# BT.net
KiCad netlist of a schematic drawn in EasyEDA
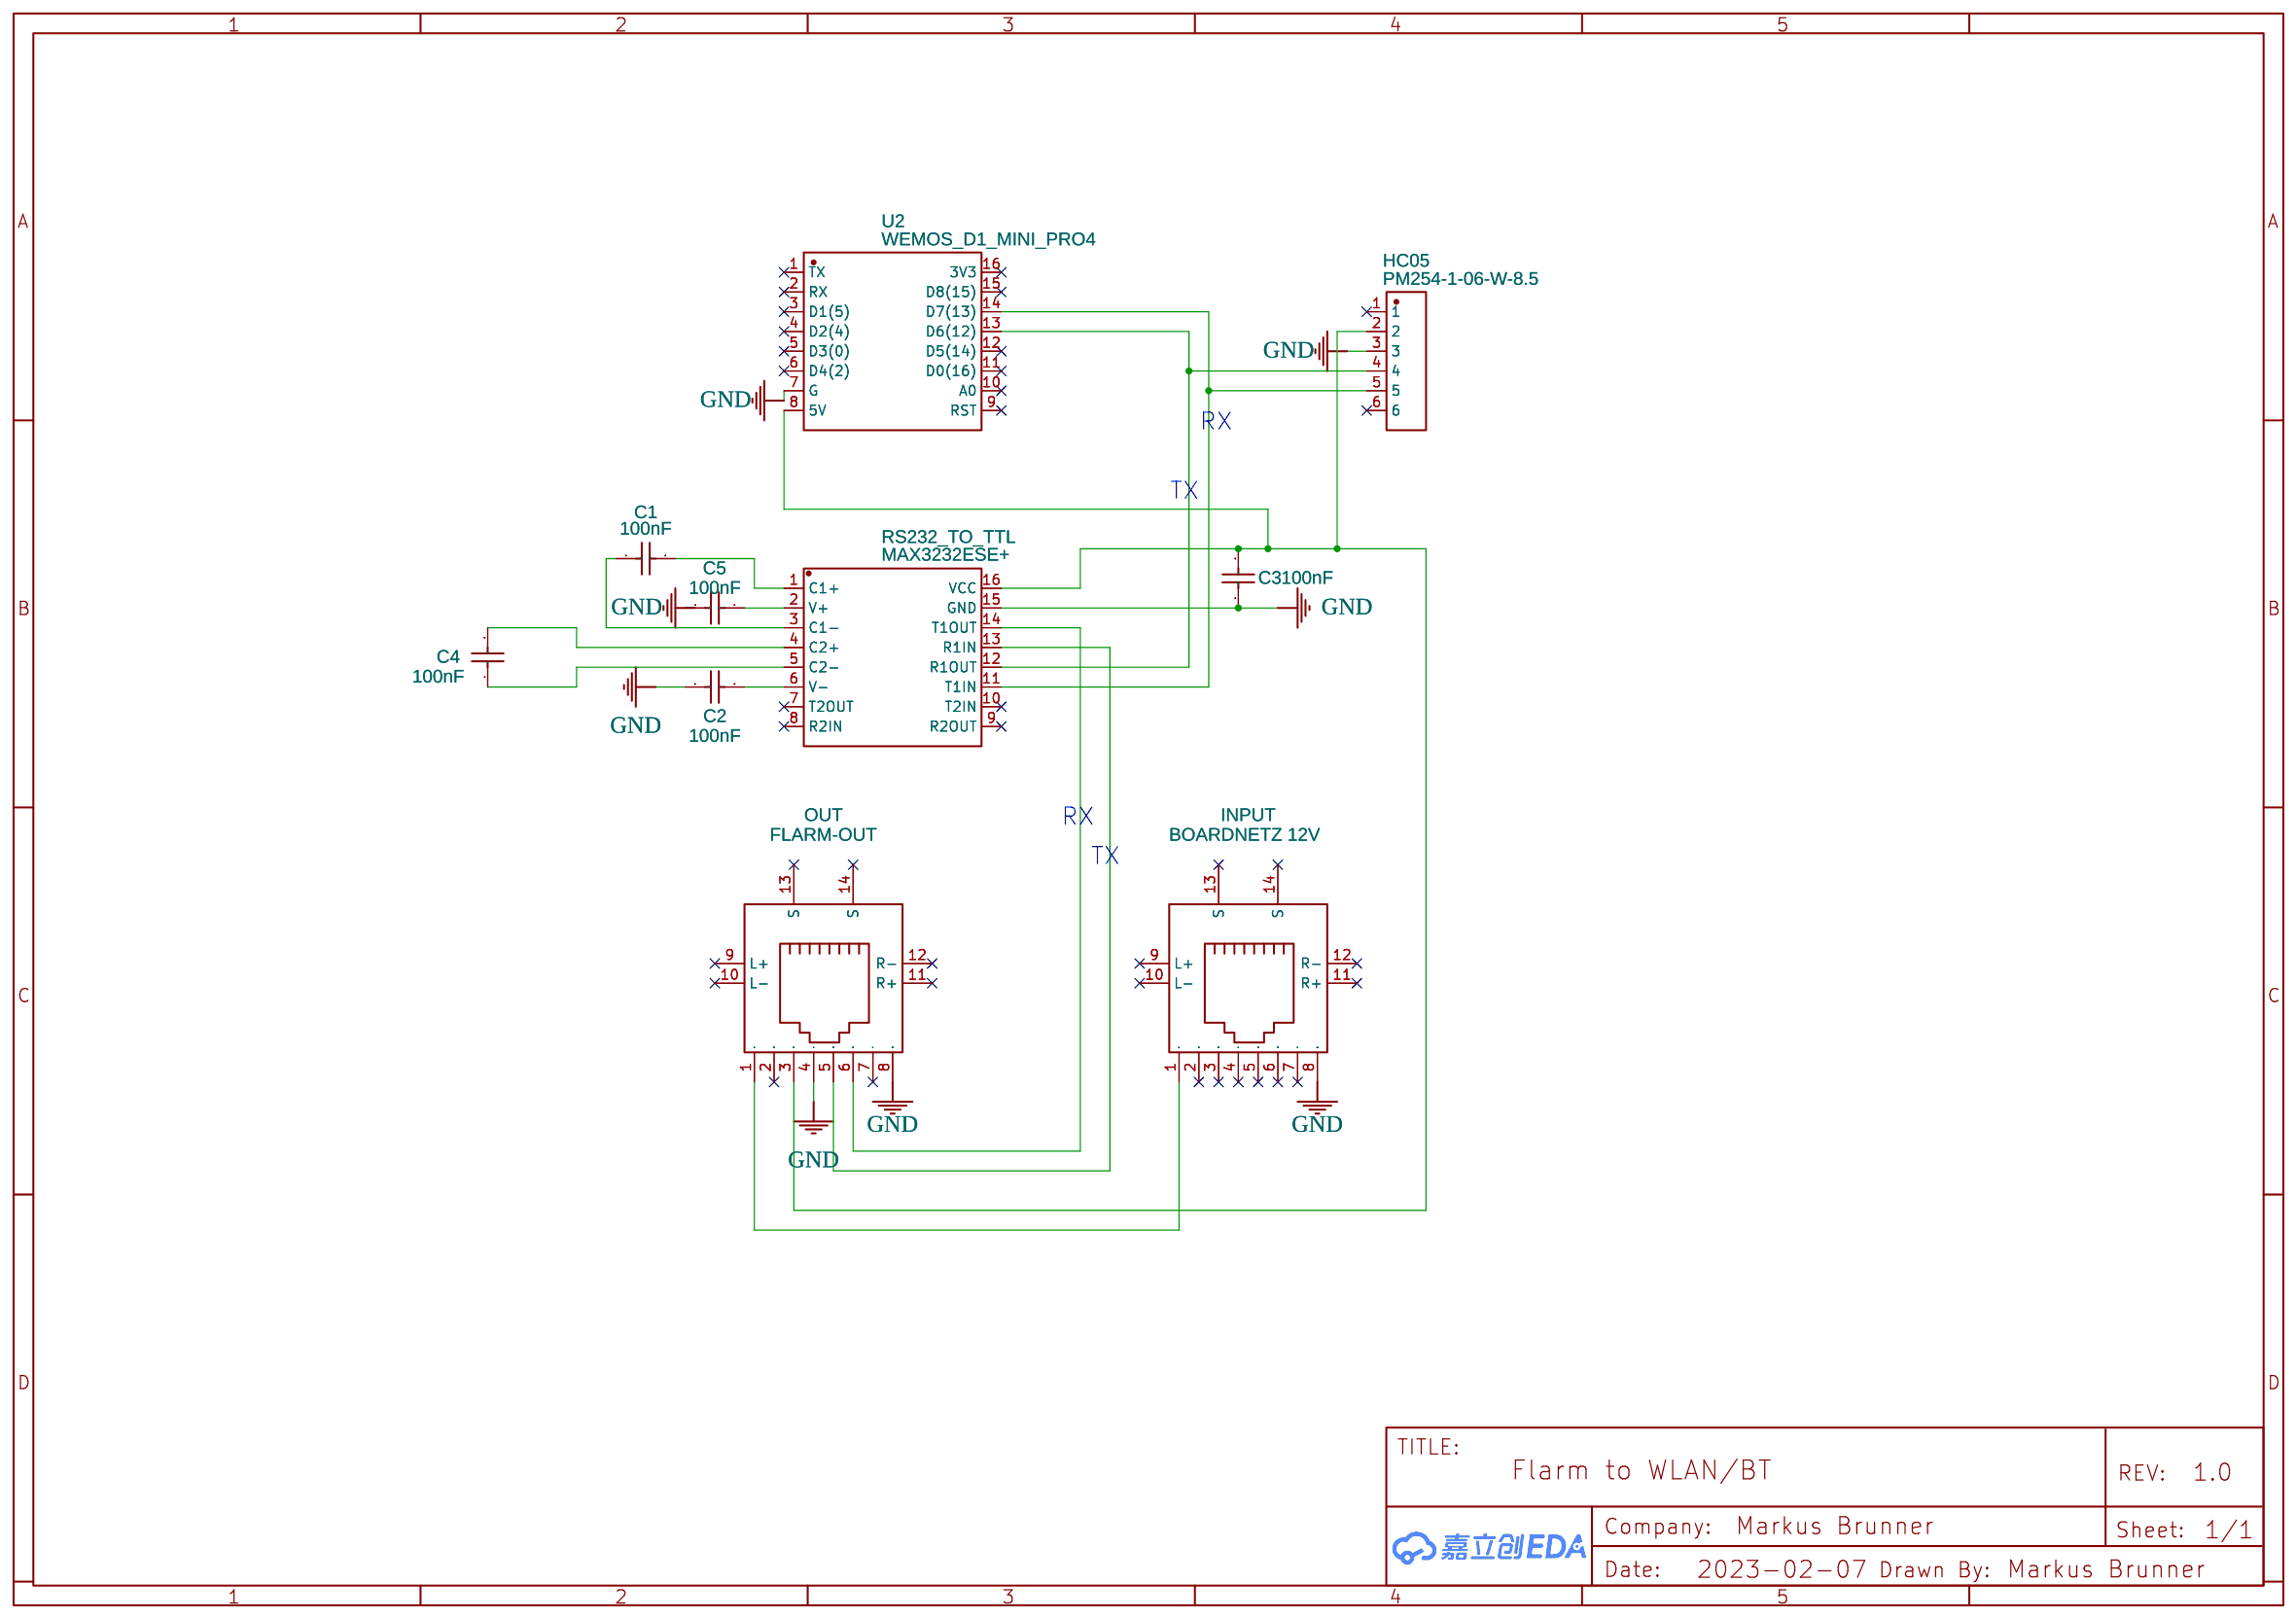
[diagram p0: schematic sheet]

(export (version "E")
  (design (tool "Eeschema 10.0.6"))
  (components
    (comp (ref "C1")
      (value "100nF")
      (fields
        (field (name "BOM_Manufacturer Part") "CL05B104KO5NNNC")
        (field (name "BOM_Supplier Part") "C1525")
      )
      (libsource (lib "") (part "CL05B104KO5NNNC"))
    )
    (comp (ref "C2")
      (value "100nF")
      (fields
        (field (name "BOM_Manufacturer Part") "CL05B104KO5NNNC")
        (field (name "BOM_Supplier Part") "C1525")
      )
      (libsource (lib "") (part "CL05B104KO5NNNC"))
    )
    (comp (ref "C3")
      (value "100nF")
      (fields
        (field (name "BOM_Manufacturer Part") "CL05B104KO5NNNC")
        (field (name "BOM_Supplier Part") "C1525")
      )
      (libsource (lib "") (part "CL05B104KO5NNNC_1"))
    )
    (comp (ref "C4")
      (value "100nF")
      (fields
        (field (name "BOM_Manufacturer Part") "CL05B104KO5NNNC")
        (field (name "BOM_Supplier Part") "C1525")
      )
      (libsource (lib "") (part "CL05B104KO5NNNC_1"))
    )
    (comp (ref "C5")
      (value "100nF")
      (fields
        (field (name "BOM_Manufacturer Part") "CL05B104KO5NNNC")
        (field (name "BOM_Supplier Part") "C1525")
      )
      (libsource (lib "") (part "CL05B104KO5NNNC"))
    )
    (comp (ref "HC05")
      (value "PM254-1-06-W-8.5")
      (fields (field (name "BOM_Supplier Part") "C2897388"))
      (libsource (lib "") (part "PM254-1-06-W-8.5"))
    )
    (comp (ref "INPUT")
      (value "BOARDNETZ 12V")
      (fields
        (field (name "BOM_Manufacturer Part") "R-RJ45R08P-C000")
        (field (name "BOM_Supplier Part") "C386757")
      )
      (libsource (lib "") (part "R-RJ45R08P-C000"))
    )
    (comp (ref "OUT")
      (value "FLARM-OUT")
      (fields
        (field (name "BOM_Manufacturer Part") "R-RJ45R08P-C000")
        (field (name "BOM_Supplier Part") "C386757")
      )
      (libsource (lib "") (part "R-RJ45R08P-C000_1"))
    )
    (comp (ref "RS232_TO_TTL")
      (value "MAX3232ESE+")
      (fields (field (name "BOM_Supplier Part") "C143435"))
      (libsource (lib "") (part "MAX3232ESE+"))
    )
    (comp (ref "U2")
      (value "WEMOS_D1_MINI_PRO4")
      (fields
        (field (name "BOM_Manufacturer Part") "Wemos_D1_mini_Pro4")
        (field (name "BOM_Supplier Part") "C2837266")
      )
      (libsource (lib "") (part "WEMOS_D1_MINI_PRO4"))
    )
  )
  (nets
    (net (code "1") (name "GND") (class "Default")
      (node (ref "C2") (pin "1") (pinfunction "1_1") (pintype "input"))
      (node (ref "C3") (pin "1") (pinfunction "1_1") (pintype "input"))
      (node (ref "C5") (pin "1") (pinfunction "1_1") (pintype "input"))
      (node (ref "HC05") (pin "3") (pinfunction "3_3") (pintype "unspecified"))
      (node (ref "INPUT") (pin "8") (pinfunction "8_8") (pintype "unspecified"))
      (node (ref "OUT") (pin "4") (pinfunction "4_4") (pintype "unspecified"))
      (node (ref "OUT") (pin "8") (pinfunction "8_8") (pintype "unspecified"))
      (node (ref "RS232_TO_TTL") (pin "15") (pinfunction "GND_15") (pintype "unspecified"))
      (node (ref "U2") (pin "7") (pinfunction "G_7") (pintype "unspecified"))
    )
    (net (code "2") (name "Net-(INPUT-Pad1)") (class "Default")
      (node (ref "INPUT") (pin "1") (pinfunction "1_1") (pintype "unspecified"))
      (node (ref "OUT") (pin "1") (pinfunction "1_1") (pintype "unspecified"))
    )
    (net (code "3") (name "Net-(RS232_TO_TTL-C1+)") (class "Default")
      (node (ref "C1") (pin "2") (pinfunction "2_2") (pintype "input"))
      (node (ref "RS232_TO_TTL") (pin "1") (pinfunction "C1+_1") (pintype "unspecified"))
    )
    (net (code "4") (name "Net-(RS232_TO_TTL-C1-)") (class "Default")
      (node (ref "C1") (pin "1") (pinfunction "1_1") (pintype "input"))
      (node (ref "RS232_TO_TTL") (pin "3") (pinfunction "C1-_3") (pintype "unspecified"))
    )
    (net (code "5") (name "Net-(RS232_TO_TTL-C2+)") (class "Default")
      (node (ref "C4") (pin "2") (pinfunction "2_2") (pintype "input"))
      (node (ref "RS232_TO_TTL") (pin "4") (pinfunction "C2+_4") (pintype "unspecified"))
    )
    (net (code "6") (name "Net-(RS232_TO_TTL-C2-)") (class "Default")
      (node (ref "C4") (pin "1") (pinfunction "1_1") (pintype "input"))
      (node (ref "RS232_TO_TTL") (pin "5") (pinfunction "C2-_5") (pintype "unspecified"))
    )
    (net (code "7") (name "Net-(RS232_TO_TTL-R1IN)") (class "Default")
      (node (ref "OUT") (pin "5") (pinfunction "5_5") (pintype "unspecified"))
      (node (ref "RS232_TO_TTL") (pin "13") (pinfunction "R1IN_13") (pintype "unspecified"))
    )
    (net (code "8") (name "Net-(RS232_TO_TTL-R1OUT)") (class "Default")
      (node (ref "HC05") (pin "4") (pinfunction "4_4") (pintype "unspecified"))
      (node (ref "RS232_TO_TTL") (pin "12") (pinfunction "R1OUT_12") (pintype "unspecified"))
      (node (ref "U2") (pin "13") (pinfunction "D6(12)_13") (pintype "unspecified"))
    )
    (net (code "9") (name "Net-(RS232_TO_TTL-T1IN)") (class "Default")
      (node (ref "HC05") (pin "5") (pinfunction "5_5") (pintype "unspecified"))
      (node (ref "RS232_TO_TTL") (pin "11") (pinfunction "T1IN_11") (pintype "unspecified"))
      (node (ref "U2") (pin "14") (pinfunction "D7(13)_14") (pintype "unspecified"))
    )
    (net (code "10") (name "Net-(RS232_TO_TTL-T1OUT)") (class "Default")
      (node (ref "OUT") (pin "6") (pinfunction "6_6") (pintype "unspecified"))
      (node (ref "RS232_TO_TTL") (pin "14") (pinfunction "T1OUT_14") (pintype "unspecified"))
    )
    (net (code "11") (name "Net-(RS232_TO_TTL-V+)") (class "Default")
      (node (ref "C5") (pin "2") (pinfunction "2_2") (pintype "input"))
      (node (ref "RS232_TO_TTL") (pin "2") (pinfunction "V+_2") (pintype "unspecified"))
    )
    (net (code "12") (name "Net-(RS232_TO_TTL-V-)") (class "Default")
      (node (ref "C2") (pin "2") (pinfunction "2_2") (pintype "input"))
      (node (ref "RS232_TO_TTL") (pin "6") (pinfunction "V-_6") (pintype "unspecified"))
    )
    (net (code "13") (name "Net-(RS232_TO_TTL-VCC)") (class "Default")
      (node (ref "C3") (pin "2") (pinfunction "2_2") (pintype "input"))
      (node (ref "HC05") (pin "2") (pinfunction "2_2") (pintype "unspecified"))
      (node (ref "OUT") (pin "3") (pinfunction "3_3") (pintype "unspecified"))
      (node (ref "RS232_TO_TTL") (pin "16") (pinfunction "VCC_16") (pintype "unspecified"))
      (node (ref "U2") (pin "8") (pinfunction "5V_8") (pintype "unspecified"))
    )
    (net (code "14") (name "unconnected-(HC05-Pad1)") (class "Default")
      (node (ref "HC05") (pin "1") (pinfunction "1_1") (pintype "unspecified+no_connect"))
    )
    (net (code "15") (name "unconnected-(HC05-Pad6)") (class "Default")
      (node (ref "HC05") (pin "6") (pinfunction "6_6") (pintype "unspecified+no_connect"))
    )
    (net (code "16") (name "unconnected-(INPUT-L+-Pad9)") (class "Default")
      (node (ref "INPUT") (pin "9") (pinfunction "L+_9") (pintype "unspecified+no_connect"))
    )
    (net (code "17") (name "unconnected-(INPUT-L--Pad10)") (class "Default")
      (node (ref "INPUT") (pin "10") (pinfunction "L-_10") (pintype "unspecified+no_connect"))
    )
    (net (code "18") (name "unconnected-(INPUT-Pad2)") (class "Default")
      (node (ref "INPUT") (pin "2") (pinfunction "2_2") (pintype "unspecified+no_connect"))
    )
    (net (code "19") (name "unconnected-(INPUT-Pad3)") (class "Default")
      (node (ref "INPUT") (pin "3") (pinfunction "3_3") (pintype "unspecified+no_connect"))
    )
    (net (code "20") (name "unconnected-(INPUT-Pad4)") (class "Default")
      (node (ref "INPUT") (pin "4") (pinfunction "4_4") (pintype "unspecified+no_connect"))
    )
    (net (code "21") (name "unconnected-(INPUT-Pad5)") (class "Default")
      (node (ref "INPUT") (pin "5") (pinfunction "5_5") (pintype "unspecified+no_connect"))
    )
    (net (code "22") (name "unconnected-(INPUT-Pad6)") (class "Default")
      (node (ref "INPUT") (pin "6") (pinfunction "6_6") (pintype "unspecified+no_connect"))
    )
    (net (code "23") (name "unconnected-(INPUT-Pad7)") (class "Default")
      (node (ref "INPUT") (pin "7") (pinfunction "7_7") (pintype "unspecified+no_connect"))
    )
    (net (code "24") (name "unconnected-(INPUT-R+-Pad11)") (class "Default")
      (node (ref "INPUT") (pin "11") (pinfunction "R+_11") (pintype "unspecified+no_connect"))
    )
    (net (code "25") (name "unconnected-(INPUT-R--Pad12)") (class "Default")
      (node (ref "INPUT") (pin "12") (pinfunction "R-_12") (pintype "unspecified+no_connect"))
    )
    (net (code "26") (name "unconnected-(INPUT-S-Pad13)") (class "Default")
      (node (ref "INPUT") (pin "13") (pinfunction "S_13") (pintype "unspecified+no_connect"))
    )
    (net (code "27") (name "unconnected-(INPUT-S-Pad14)") (class "Default")
      (node (ref "INPUT") (pin "14") (pinfunction "S_14") (pintype "unspecified+no_connect"))
    )
    (net (code "28") (name "unconnected-(OUT-L+-Pad9)") (class "Default")
      (node (ref "OUT") (pin "9") (pinfunction "L+_9") (pintype "unspecified+no_connect"))
    )
    (net (code "29") (name "unconnected-(OUT-L--Pad10)") (class "Default")
      (node (ref "OUT") (pin "10") (pinfunction "L-_10") (pintype "unspecified+no_connect"))
    )
    (net (code "30") (name "unconnected-(OUT-Pad2)") (class "Default")
      (node (ref "OUT") (pin "2") (pinfunction "2_2") (pintype "unspecified+no_connect"))
    )
    (net (code "31") (name "unconnected-(OUT-Pad7)") (class "Default")
      (node (ref "OUT") (pin "7") (pinfunction "7_7") (pintype "unspecified+no_connect"))
    )
    (net (code "32") (name "unconnected-(OUT-R+-Pad11)") (class "Default")
      (node (ref "OUT") (pin "11") (pinfunction "R+_11") (pintype "unspecified+no_connect"))
    )
    (net (code "33") (name "unconnected-(OUT-R--Pad12)") (class "Default")
      (node (ref "OUT") (pin "12") (pinfunction "R-_12") (pintype "unspecified+no_connect"))
    )
    (net (code "34") (name "unconnected-(OUT-S-Pad13)") (class "Default")
      (node (ref "OUT") (pin "13") (pinfunction "S_13") (pintype "unspecified+no_connect"))
    )
    (net (code "35") (name "unconnected-(OUT-S-Pad14)") (class "Default")
      (node (ref "OUT") (pin "14") (pinfunction "S_14") (pintype "unspecified+no_connect"))
    )
    (net (code "36") (name "unconnected-(RS232_TO_TTL-R2IN-Pad8)") (class "Default")
      (node (ref "RS232_TO_TTL") (pin "8") (pinfunction "R2IN_8") (pintype "unspecified+no_connect"))
    )
    (net (code "37") (name "unconnected-(RS232_TO_TTL-R2OUT-Pad9)") (class "Default")
      (node (ref "RS232_TO_TTL") (pin "9") (pinfunction "R2OUT_9") (pintype "unspecified+no_connect"))
    )
    (net (code "38") (name "unconnected-(RS232_TO_TTL-T2IN-Pad10)") (class "Default")
      (node (ref "RS232_TO_TTL") (pin "10") (pinfunction "T2IN_10") (pintype "unspecified+no_connect"))
    )
    (net (code "39") (name "unconnected-(RS232_TO_TTL-T2OUT-Pad7)") (class "Default")
      (node (ref "RS232_TO_TTL") (pin "7") (pinfunction "T2OUT_7") (pintype "unspecified+no_connect"))
    )
    (net (code "40") (name "unconnected-(U2-3V3-Pad16)") (class "Default")
      (node (ref "U2") (pin "16") (pinfunction "3V3_16") (pintype "unspecified+no_connect"))
    )
    (net (code "41") (name "unconnected-(U2-A0-Pad10)") (class "Default")
      (node (ref "U2") (pin "10") (pinfunction "A0_10") (pintype "unspecified+no_connect"))
    )
    (net (code "42") (name "unconnected-(U2-D0(16)-Pad11)") (class "Default")
      (node (ref "U2") (pin "11") (pinfunction "D0(16)_11") (pintype "unspecified+no_connect"))
    )
    (net (code "43") (name "unconnected-(U2-D1(5)-Pad3)") (class "Default")
      (node (ref "U2") (pin "3") (pinfunction "D1(5)_3") (pintype "unspecified+no_connect"))
    )
    (net (code "44") (name "unconnected-(U2-D2(4)-Pad4)") (class "Default")
      (node (ref "U2") (pin "4") (pinfunction "D2(4)_4") (pintype "unspecified+no_connect"))
    )
    (net (code "45") (name "unconnected-(U2-D3(0)-Pad5)") (class "Default")
      (node (ref "U2") (pin "5") (pinfunction "D3(0)_5") (pintype "unspecified+no_connect"))
    )
    (net (code "46") (name "unconnected-(U2-D4(2)-Pad6)") (class "Default")
      (node (ref "U2") (pin "6") (pinfunction "D4(2)_6") (pintype "unspecified+no_connect"))
    )
    (net (code "47") (name "unconnected-(U2-D5(14)-Pad12)") (class "Default")
      (node (ref "U2") (pin "12") (pinfunction "D5(14)_12") (pintype "unspecified+no_connect"))
    )
    (net (code "48") (name "unconnected-(U2-D8(15)-Pad15)") (class "Default")
      (node (ref "U2") (pin "15") (pinfunction "D8(15)_15") (pintype "unspecified+no_connect"))
    )
    (net (code "49") (name "unconnected-(U2-RST-Pad9)") (class "Default")
      (node (ref "U2") (pin "9") (pinfunction "RST_9") (pintype "unspecified+no_connect"))
    )
    (net (code "50") (name "unconnected-(U2-RX-Pad2)") (class "Default")
      (node (ref "U2") (pin "2") (pinfunction "RX_2") (pintype "unspecified+no_connect"))
    )
    (net (code "51") (name "unconnected-(U2-TX-Pad1)") (class "Default")
      (node (ref "U2") (pin "1") (pinfunction "TX_1") (pintype "unspecified+no_connect"))
    )
  )
)
